# ESP8266_MySensorsGateway_v1_5.net
KiCad netlist of a schematic drawn in EAGLE
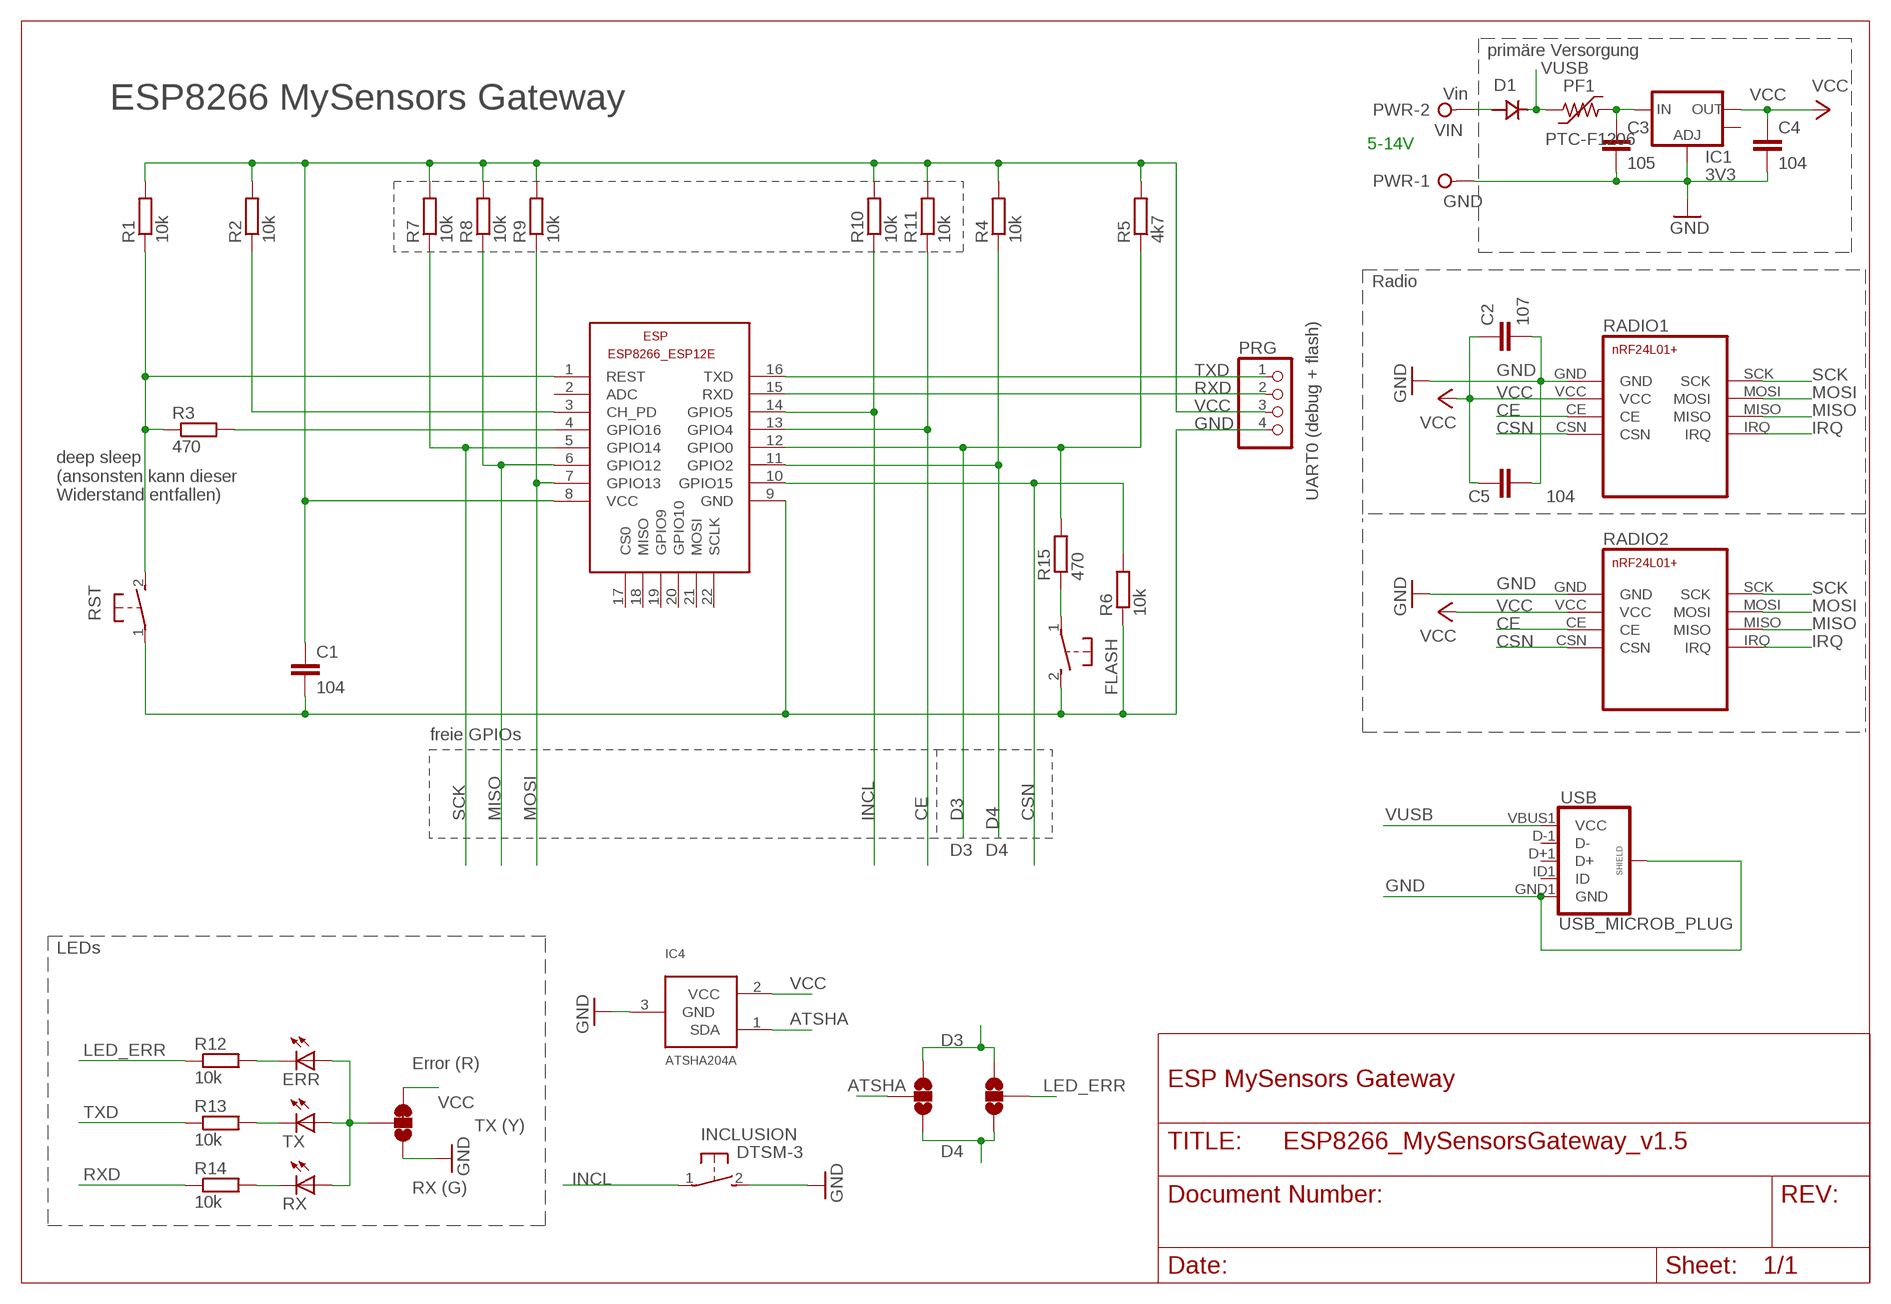
[diagram p0: schematic, sheet 1]

(export (version "E")
  (design (tool "Eeschema 10.0.6"))
  (components
    (comp (ref "C1")
      (value "104")
      (footprint "eagle-import:C0805")
      (libsource (lib "eagle-import") (part "C-EUC0805"))
    )
    (comp (ref "C2")
      (value "107")
      (footprint "eagle-import:MY1210")
      (libsource (lib "eagle-import") (part "C"))
    )
    (comp (ref "C3")
      (value "105")
      (footprint "eagle-import:C0805")
      (libsource (lib "eagle-import") (part "C-EUC0805"))
    )
    (comp (ref "C4")
      (value "104")
      (footprint "eagle-import:C0805")
      (libsource (lib "eagle-import") (part "C-EUC0805"))
    )
    (comp (ref "C5")
      (value "104")
      (footprint "eagle-import:C0805")
      (libsource (lib "eagle-import") (part "C-EUC0805"))
    )
    (comp (ref "D1")
      (value "SS14")
      (footprint "eagle-import:DO214")
      (libsource (lib "eagle-import") (part "SS14"))
    )
    (comp (ref "ERR")
      (value "R")
      (footprint "eagle-import:CHIPLED_1206")
      (libsource (lib "eagle-import") (part "LEDCHIPLED_1206"))
    )
    (comp (ref "ESP")
      (value "µC")
      (footprint "eagle-import:ESP8266-ESP12E")
      (libsource (lib "eagle-import") (part "ESP8266-12EESP8266-ESP12E"))
    )
    (comp (ref "FLASH")
      (value "DTSM-3")
      (footprint "eagle-import:DTSM-3")
      (libsource (lib "eagle-import") (part "DTSM-3"))
    )
    (comp (ref "IC1")
      (value "3V3")
      (footprint "eagle-import:SOT223")
      (libsource (lib "eagle-import") (part "V_REG_LM1117SOT223"))
    )
    (comp (ref "IC4")
      (value "ATSHA204A")
      (footprint "eagle-import:SOT23")
      (libsource (lib "eagle-import") (part "ATSHA204A"))
    )
    (comp (ref "INCLUSION")
      (value "DTSM-3")
      (footprint "eagle-import:DTSM-3")
      (libsource (lib "eagle-import") (part "DTSM-3"))
    )
    (comp (ref "PF1")
      (value "PTC-F1206")
      (footprint "eagle-import:F1206")
      (libsource (lib "eagle-import") (part "PTC-F1206"))
    )
    (comp (ref "PRG")
      (value "PINHD-1X4_S")
      (footprint "eagle-import:1X04")
      (libsource (lib "eagle-import") (part "PINHD-1X4_S"))
    )
    (comp (ref "PWR")
      (value "Vin")
      (footprint "eagle-import:W237-132")
      (libsource (lib "eagle-import") (part "W237-02P"))
    )
    (comp (ref "R1")
      (value "10k")
      (footprint "eagle-import:R0805")
      (libsource (lib "eagle-import") (part "resistor_R-EU_R0805"))
    )
    (comp (ref "R2")
      (value "10k")
      (footprint "eagle-import:R0805")
      (libsource (lib "eagle-import") (part "resistor_R-EU_R0805"))
    )
    (comp (ref "R3")
      (value "470")
      (footprint "eagle-import:R0805")
      (libsource (lib "eagle-import") (part "resistor_R-EU_R0805"))
    )
    (comp (ref "R4")
      (value "10k")
      (footprint "eagle-import:R0805")
      (libsource (lib "eagle-import") (part "resistor_R-EU_R0805"))
    )
    (comp (ref "R5")
      (value "4k7")
      (footprint "eagle-import:R0805")
      (libsource (lib "eagle-import") (part "resistor_R-EU_R0805"))
    )
    (comp (ref "R6")
      (value "10k")
      (footprint "eagle-import:R0805")
      (libsource (lib "eagle-import") (part "resistor_R-EU_R0805"))
    )
    (comp (ref "R7")
      (value "10k")
      (footprint "eagle-import:R0805")
      (libsource (lib "eagle-import") (part "resistor_R-EU_R0805"))
    )
    (comp (ref "R8")
      (value "10k")
      (footprint "eagle-import:R0805")
      (libsource (lib "eagle-import") (part "resistor_R-EU_R0805"))
    )
    (comp (ref "R9")
      (value "10k")
      (footprint "eagle-import:R0805")
      (libsource (lib "eagle-import") (part "resistor_R-EU_R0805"))
    )
    (comp (ref "R10")
      (value "10k")
      (footprint "eagle-import:R0805")
      (libsource (lib "eagle-import") (part "resistor_R-EU_R0805"))
    )
    (comp (ref "R11")
      (value "10k")
      (footprint "eagle-import:R0805")
      (libsource (lib "eagle-import") (part "resistor_R-EU_R0805"))
    )
    (comp (ref "R12")
      (value "10k")
      (footprint "eagle-import:R0805")
      (libsource (lib "eagle-import") (part "R-EU_R0805"))
    )
    (comp (ref "R13")
      (value "10k")
      (footprint "eagle-import:R0805")
      (libsource (lib "eagle-import") (part "R-EU_R0805"))
    )
    (comp (ref "R14")
      (value "10k")
      (footprint "eagle-import:R0805")
      (libsource (lib "eagle-import") (part "R-EU_R0805"))
    )
    (comp (ref "R15")
      (value "470")
      (footprint "eagle-import:R0805")
      (libsource (lib "eagle-import") (part "resistor_R-EU_R0805"))
    )
    (comp (ref "RADIO1")
      (value "NRF24L01+")
      (footprint "eagle-import:NRF24L01+")
      (libsource (lib "eagle-import") (part "NRF24L01+"))
    )
    (comp (ref "RADIO2")
      (value "NRF24L01+NRF24L01+MINI")
      (footprint "eagle-import:NRF24L01+MINI")
      (libsource (lib "eagle-import") (part "NRF24L01+NRF24L01+MINI"))
    )
    (comp (ref "RST")
      (value "DTSM-3")
      (footprint "eagle-import:DTSM-3")
      (libsource (lib "eagle-import") (part "DTSM-3"))
    )
    (comp (ref "RX")
      (value "G")
      (footprint "eagle-import:CHIPLED_1206")
      (libsource (lib "eagle-import") (part "LEDCHIPLED_1206"))
    )
    (comp (ref "SJ1")
      (value "JUMPER-PAD-3-2OF3_NC_BY_TRACE_SMALL")
      (footprint "eagle-import:PAD-JUMPER-3-2OF3_NC_BY_TRACE_YES_SILK_FULL_BOX")
      (libsource (lib "eagle-import") (part "JUMPER-PAD-3-2OF3_NC_BY_TRACE_SMALL"))
    )
    (comp (ref "SJ2")
      (value "JUMPER-PAD-3-NOYES_SILK")
      (footprint "eagle-import:PAD-JUMPER-3-NO_YES_SILK")
      (libsource (lib "eagle-import") (part "JUMPER-PAD-3-NOYES_SILK"))
    )
    (comp (ref "SJ3")
      (value "JUMPER-PAD-3-NOYES_SILK")
      (footprint "eagle-import:PAD-JUMPER-3-NO_YES_SILK")
      (libsource (lib "eagle-import") (part "JUMPER-PAD-3-NOYES_SILK"))
    )
    (comp (ref "TX")
      (value "Y")
      (footprint "eagle-import:CHIPLED_1206")
      (libsource (lib "eagle-import") (part "LEDCHIPLED_1206"))
    )
    (comp (ref "USB")
      (value "USB_MICROB_PLUG")
      (footprint "eagle-import:USB-B-MICRO-SMD_V03_HOLE")
      (libsource (lib "eagle-import") (part "USB_MICROB_PLUG"))
    )
  )
  (nets
    (net (code "1") (name "/ATSHA") (class "Default")
      (node (ref "IC4") (pin "1") (pinfunction "SDA_1") (pintype "bidirectional"))
      (node (ref "SJ2") (pin "2") (pinfunction "2_2") (pintype "passive"))
    )
    (net (code "2") (name "/CE") (class "Default")
      (node (ref "ESP") (pin "13") (pinfunction "GPIO4_13") (pintype "bidirectional"))
      (node (ref "R11") (pin "1") (pinfunction "1_1") (pintype "passive"))
      (node (ref "RADIO1") (pin "CE") (pinfunction "CE_CE") (pintype "bidirectional"))
      (node (ref "RADIO2") (pin "CE") (pinfunction "CE_CE") (pintype "bidirectional"))
    )
    (net (code "3") (name "/CSN") (class "Default")
      (node (ref "ESP") (pin "10") (pinfunction "GPIO15_10") (pintype "bidirectional"))
      (node (ref "R6") (pin "2") (pinfunction "2_2") (pintype "passive"))
      (node (ref "RADIO1") (pin "CSN") (pinfunction "CSN_CSN") (pintype "bidirectional"))
      (node (ref "RADIO2") (pin "CSN") (pinfunction "CSN_CSN") (pintype "bidirectional"))
    )
    (net (code "4") (name "/D3") (class "Default")
      (node (ref "ESP") (pin "12") (pinfunction "GPIO0_12") (pintype "bidirectional"))
      (node (ref "R15") (pin "2") (pinfunction "2_2") (pintype "passive"))
      (node (ref "R5") (pin "1") (pinfunction "1_1") (pintype "passive"))
      (node (ref "SJ2") (pin "3") (pinfunction "3_3") (pintype "passive"))
      (node (ref "SJ3") (pin "1") (pinfunction "1_1") (pintype "passive"))
    )
    (net (code "5") (name "/D4") (class "Default")
      (node (ref "ESP") (pin "11") (pinfunction "GPIO2_11") (pintype "bidirectional"))
      (node (ref "R4") (pin "1") (pinfunction "1_1") (pintype "passive"))
      (node (ref "SJ2") (pin "1") (pinfunction "1_1") (pintype "passive"))
      (node (ref "SJ3") (pin "3") (pinfunction "3_3") (pintype "passive"))
    )
    (net (code "6") (name "/INCL") (class "Default")
      (node (ref "ESP") (pin "14") (pinfunction "GPIO5_14") (pintype "bidirectional"))
      (node (ref "INCLUSION") (pin "1") (pinfunction "1_1") (pintype "passive"))
      (node (ref "R10") (pin "1") (pinfunction "1_1") (pintype "passive"))
    )
    (net (code "7") (name "/IRQ") (class "Default")
      (node (ref "RADIO1") (pin "IRQ") (pinfunction "IRQ_IRQ") (pintype "bidirectional"))
      (node (ref "RADIO2") (pin "IRQ") (pinfunction "IRQ_IRQ") (pintype "bidirectional"))
    )
    (net (code "8") (name "/LED_ERR") (class "Default")
      (node (ref "R12") (pin "1") (pinfunction "1_1") (pintype "passive"))
      (node (ref "SJ3") (pin "2") (pinfunction "2_2") (pintype "passive"))
    )
    (net (code "9") (name "/MISO") (class "Default")
      (node (ref "ESP") (pin "6") (pinfunction "GPIO12_6") (pintype "bidirectional"))
      (node (ref "R8") (pin "1") (pinfunction "1_1") (pintype "passive"))
      (node (ref "RADIO1") (pin "MISO") (pinfunction "MISO_MISO") (pintype "bidirectional"))
      (node (ref "RADIO2") (pin "MISO") (pinfunction "MISO_MISO") (pintype "bidirectional"))
    )
    (net (code "10") (name "/MOSI") (class "Default")
      (node (ref "ESP") (pin "7") (pinfunction "GPIO13_7") (pintype "bidirectional"))
      (node (ref "R9") (pin "1") (pinfunction "1_1") (pintype "passive"))
      (node (ref "RADIO1") (pin "MOSI") (pinfunction "MOSI_MOSI") (pintype "bidirectional"))
      (node (ref "RADIO2") (pin "MOSI") (pinfunction "MOSI_MOSI") (pintype "bidirectional"))
    )
    (net (code "11") (name "/RXD") (class "Default")
      (node (ref "ESP") (pin "15") (pinfunction "RXD_15") (pintype "bidirectional"))
      (node (ref "PRG") (pin "2") (pinfunction "2_2") (pintype "passive"))
      (node (ref "R14") (pin "1") (pinfunction "1_1") (pintype "passive"))
    )
    (net (code "12") (name "/SCK") (class "Default")
      (node (ref "ESP") (pin "5") (pinfunction "GPIO14_5") (pintype "bidirectional"))
      (node (ref "R7") (pin "1") (pinfunction "1_1") (pintype "passive"))
      (node (ref "RADIO1") (pin "SCK") (pinfunction "SCK_SCK") (pintype "bidirectional"))
      (node (ref "RADIO2") (pin "SCK") (pinfunction "SCK_SCK") (pintype "bidirectional"))
    )
    (net (code "13") (name "/TXD") (class "Default")
      (node (ref "ESP") (pin "16") (pinfunction "TXD_16") (pintype "bidirectional"))
      (node (ref "PRG") (pin "1") (pinfunction "1_1") (pintype "passive"))
      (node (ref "R13") (pin "1") (pinfunction "1_1") (pintype "passive"))
    )
    (net (code "14") (name "/VIN") (class "Default")
      (node (ref "D1") (pin "ANODE") (pinfunction "ANODE_ANODE") (pintype "bidirectional"))
      (node (ref "PWR") (pin "2") (pinfunction "KL_2") (pintype "passive"))
    )
    (net (code "15") (name "/VUSB") (class "Default")
      (node (ref "D1") (pin "CATHODE") (pinfunction "CATHODE_CATHODE") (pintype "bidirectional"))
      (node (ref "PF1") (pin "1") (pinfunction "1_1") (pintype "passive"))
      (node (ref "USB") (pin "VBUS1") (pinfunction "VCC_VBUS1") (pintype "bidirectional"))
    )
    (net (code "16") (name "GND") (class "Default")
      (node (ref "C1") (pin "2") (pinfunction "2_2") (pintype "passive"))
      (node (ref "C2") (pin "2") (pinfunction "2_2") (pintype "passive"))
      (node (ref "C3") (pin "2") (pinfunction "2_2") (pintype "passive"))
      (node (ref "C4") (pin "2") (pinfunction "2_2") (pintype "passive"))
      (node (ref "C5") (pin "2") (pinfunction "2_2") (pintype "passive"))
      (node (ref "ESP") (pin "9") (pinfunction "GND_9") (pintype "bidirectional"))
      (node (ref "FLASH") (pin "2") (pinfunction "2_2") (pintype "passive"))
      (node (ref "IC1") (pin "1") (pinfunction "ADJ_1") (pintype "input"))
      (node (ref "IC4") (pin "3") (pinfunction "GND_3") (pintype "bidirectional"))
      (node (ref "INCLUSION") (pin "2") (pinfunction "2_2") (pintype "passive"))
      (node (ref "PRG") (pin "4") (pinfunction "4_4") (pintype "passive"))
      (node (ref "PWR") (pin "1") (pinfunction "KL_1") (pintype "passive"))
      (node (ref "R6") (pin "1") (pinfunction "1_1") (pintype "passive"))
      (node (ref "RADIO1") (pin "GND") (pinfunction "GND_GND") (pintype "power_in"))
      (node (ref "RADIO2") (pin "GND") (pinfunction "GND_GND") (pintype "power_in"))
      (node (ref "RST") (pin "1") (pinfunction "1_1") (pintype "passive"))
      (node (ref "SJ1") (pin "1") (pinfunction "1_1") (pintype "passive"))
      (node (ref "USB") (pin "GND1") (pinfunction "GND_GND1") (pintype "bidirectional"))
      (node (ref "USB") (pin "SHIELD1") (pinfunction "SHIELD_SHIELD1") (pintype "bidirectional"))
      (node (ref "USB") (pin "SHIELD2") (pinfunction "SHIELD_SHIELD2") (pintype "bidirectional"))
      (node (ref "USB") (pin "SHIELD3") (pinfunction "SHIELD_SHIELD3") (pintype "bidirectional"))
      (node (ref "USB") (pin "SLOT1") (pinfunction "SHIELD_SLOT1") (pintype "bidirectional"))
      (node (ref "USB") (pin "SLOT2") (pinfunction "SHIELD_SLOT2") (pintype "bidirectional"))
      (node (ref "USB") (pin "TAB1") (pinfunction "SHIELD_TAB1") (pintype "bidirectional"))
      (node (ref "USB") (pin "TAB2") (pinfunction "SHIELD_TAB2") (pintype "bidirectional"))
    )
    (net (code "17") (name "Net-(ERR-PadA)") (class "Default")
      (node (ref "ERR") (pin "A") (pinfunction "A_A") (pintype "passive"))
      (node (ref "RX") (pin "A") (pinfunction "A_A") (pintype "passive"))
      (node (ref "SJ1") (pin "2") (pinfunction "2_2") (pintype "passive"))
      (node (ref "TX") (pin "A") (pinfunction "A_A") (pintype "passive"))
    )
    (net (code "18") (name "Net-(ERR-PadC)") (class "Default")
      (node (ref "ERR") (pin "C") (pinfunction "C_C") (pintype "passive"))
      (node (ref "R12") (pin "2") (pinfunction "2_2") (pintype "passive"))
    )
    (net (code "19") (name "Net-(ESP-CH_PD)") (class "Default")
      (node (ref "ESP") (pin "3") (pinfunction "CH_PD_3") (pintype "bidirectional"))
      (node (ref "R2") (pin "1") (pinfunction "1_1") (pintype "passive"))
    )
    (net (code "20") (name "Net-(ESP-GPIO16)") (class "Default")
      (node (ref "ESP") (pin "4") (pinfunction "GPIO16_4") (pintype "bidirectional"))
      (node (ref "R3") (pin "2") (pinfunction "2_2") (pintype "passive"))
    )
    (net (code "21") (name "Net-(ESP-REST)") (class "Default")
      (node (ref "ESP") (pin "1") (pinfunction "REST_1") (pintype "bidirectional"))
      (node (ref "R1") (pin "1") (pinfunction "1_1") (pintype "passive"))
      (node (ref "R3") (pin "1") (pinfunction "1_1") (pintype "passive"))
      (node (ref "RST") (pin "2") (pinfunction "2_2") (pintype "passive"))
    )
    (net (code "22") (name "Net-(FLASH-Pad1)") (class "Default")
      (node (ref "FLASH") (pin "1") (pinfunction "1_1") (pintype "passive"))
      (node (ref "R15") (pin "1") (pinfunction "1_1") (pintype "passive"))
    )
    (net (code "23") (name "Net-(IC1-IN)") (class "Default")
      (node (ref "C3") (pin "1") (pinfunction "1_1") (pintype "passive"))
      (node (ref "IC1") (pin "3") (pinfunction "IN_3") (pintype "input"))
      (node (ref "PF1") (pin "2") (pinfunction "2_2") (pintype "passive"))
    )
    (net (code "24") (name "Net-(R13-Pad2)") (class "Default")
      (node (ref "R13") (pin "2") (pinfunction "2_2") (pintype "passive"))
      (node (ref "TX") (pin "C") (pinfunction "C_C") (pintype "passive"))
    )
    (net (code "25") (name "Net-(R14-Pad2)") (class "Default")
      (node (ref "R14") (pin "2") (pinfunction "2_2") (pintype "passive"))
      (node (ref "RX") (pin "C") (pinfunction "C_C") (pintype "passive"))
    )
    (net (code "26") (name "VCC") (class "Default")
      (node (ref "C1") (pin "1") (pinfunction "1_1") (pintype "passive"))
      (node (ref "C2") (pin "1") (pinfunction "1_1") (pintype "passive"))
      (node (ref "C4") (pin "1") (pinfunction "1_1") (pintype "passive"))
      (node (ref "C5") (pin "1") (pinfunction "1_1") (pintype "passive"))
      (node (ref "ESP") (pin "8") (pinfunction "VCC_8") (pintype "bidirectional"))
      (node (ref "IC1") (pin "2") (pinfunction "OUT_2") (pintype "output"))
      (node (ref "IC4") (pin "2") (pinfunction "VCC_2") (pintype "bidirectional"))
      (node (ref "PRG") (pin "3") (pinfunction "3_3") (pintype "passive"))
      (node (ref "R1") (pin "2") (pinfunction "2_2") (pintype "passive"))
      (node (ref "R10") (pin "2") (pinfunction "2_2") (pintype "passive"))
      (node (ref "R11") (pin "2") (pinfunction "2_2") (pintype "passive"))
      (node (ref "R2") (pin "2") (pinfunction "2_2") (pintype "passive"))
      (node (ref "R4") (pin "2") (pinfunction "2_2") (pintype "passive"))
      (node (ref "R5") (pin "2") (pinfunction "2_2") (pintype "passive"))
      (node (ref "R7") (pin "2") (pinfunction "2_2") (pintype "passive"))
      (node (ref "R8") (pin "2") (pinfunction "2_2") (pintype "passive"))
      (node (ref "R9") (pin "2") (pinfunction "2_2") (pintype "passive"))
      (node (ref "RADIO1") (pin "VCC") (pinfunction "VCC_VCC") (pintype "power_in"))
      (node (ref "RADIO2") (pin "VCC") (pinfunction "VCC_VCC") (pintype "power_in"))
      (node (ref "SJ1") (pin "3") (pinfunction "3_3") (pintype "passive"))
    )
    (net (code "27") (name "unconnected-(ESP-ADC-Pad2)") (class "Default")
      (node (ref "ESP") (pin "2") (pinfunction "ADC_2") (pintype "bidirectional"))
    )
    (net (code "28") (name "unconnected-(ESP-CS0-Pad17)") (class "Default")
      (node (ref "ESP") (pin "17") (pinfunction "CS0_17") (pintype "bidirectional"))
    )
    (net (code "29") (name "unconnected-(ESP-GPIO9-Pad19)") (class "Default")
      (node (ref "ESP") (pin "19") (pinfunction "GPIO9_19") (pintype "bidirectional"))
    )
    (net (code "30") (name "unconnected-(ESP-GPIO10-Pad20)") (class "Default")
      (node (ref "ESP") (pin "20") (pinfunction "GPIO10_20") (pintype "bidirectional"))
    )
    (net (code "31") (name "unconnected-(ESP-MISO-Pad18)") (class "Default")
      (node (ref "ESP") (pin "18") (pinfunction "MISO_18") (pintype "bidirectional"))
    )
    (net (code "32") (name "unconnected-(ESP-MOSI-Pad21)") (class "Default")
      (node (ref "ESP") (pin "21") (pinfunction "MOSI_21") (pintype "bidirectional"))
    )
    (net (code "33") (name "unconnected-(ESP-SCLK-Pad22)") (class "Default")
      (node (ref "ESP") (pin "22") (pinfunction "SCLK_22") (pintype "bidirectional"))
    )
    (net (code "34") (name "unconnected-(IC1-OUT-Pad4)") (class "Default")
      (node (ref "IC1") (pin "4") (pinfunction "OUT_4") (pintype "output"))
    )
    (net (code "35") (name "unconnected-(USB-D+-PadD+1)") (class "Default")
      (node (ref "USB") (pin "D+1") (pinfunction "D+_D+1") (pintype "bidirectional"))
    )
    (net (code "36") (name "unconnected-(USB-D--PadD-1)") (class "Default")
      (node (ref "USB") (pin "D-1") (pinfunction "D-_D-1") (pintype "bidirectional"))
    )
    (net (code "37") (name "unconnected-(USB-ID-PadID1)") (class "Default")
      (node (ref "USB") (pin "ID1") (pinfunction "ID_ID1") (pintype "bidirectional"))
    )
  )
)
